# PIC32.net
KiCad netlist of a schematic drawn in EAGLE
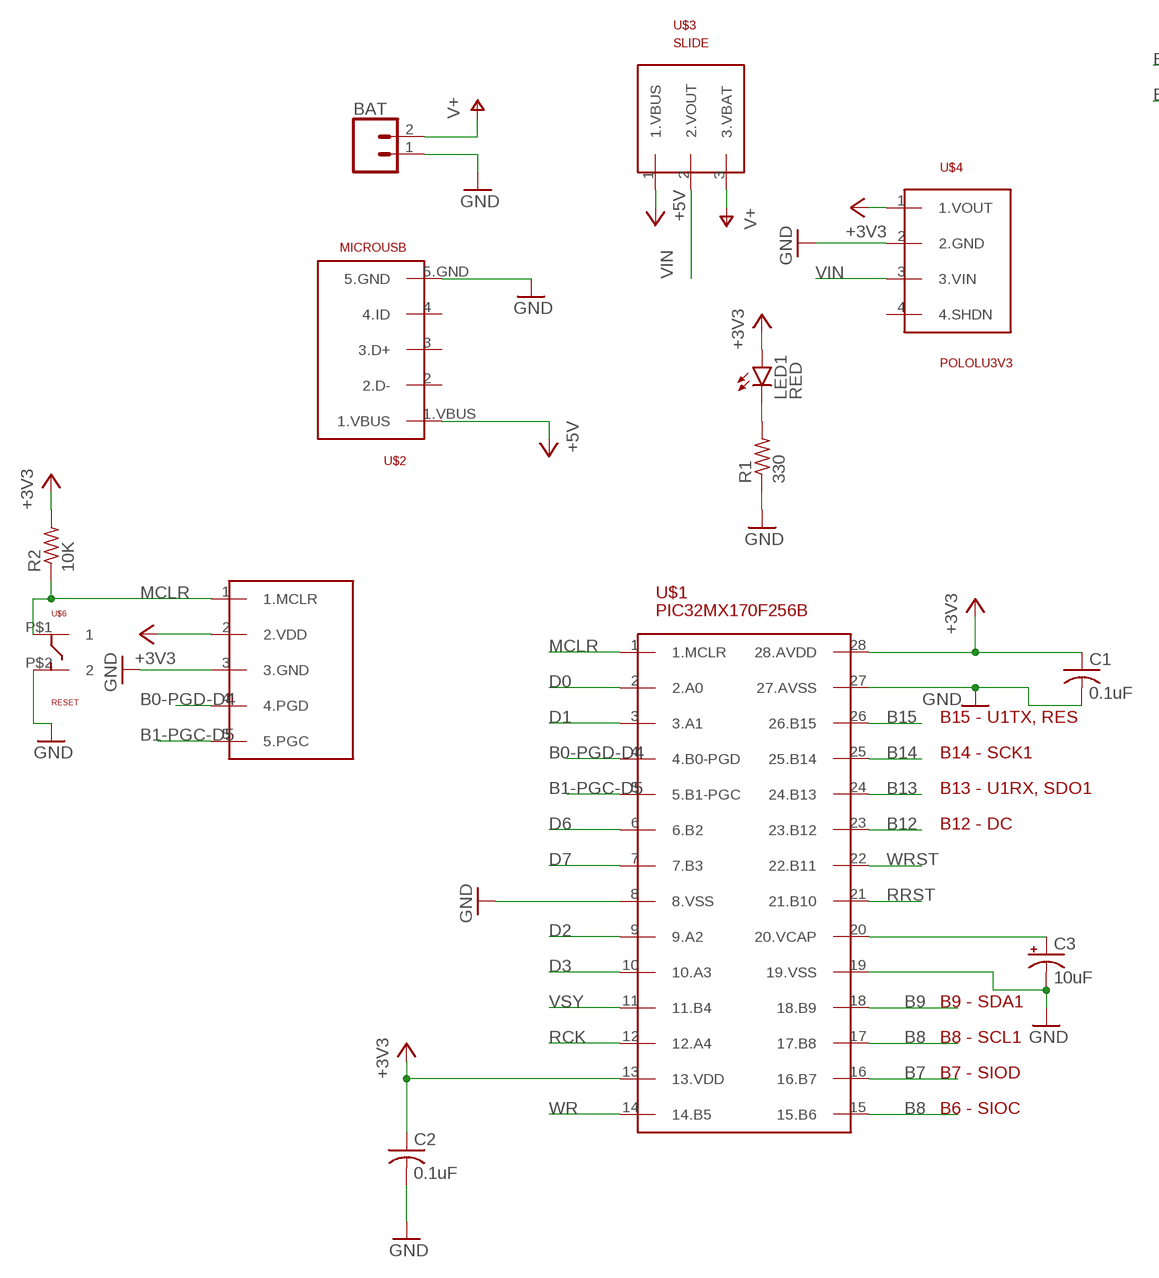
[diagram p0: schematic, sheet 1, part 1 of 2]
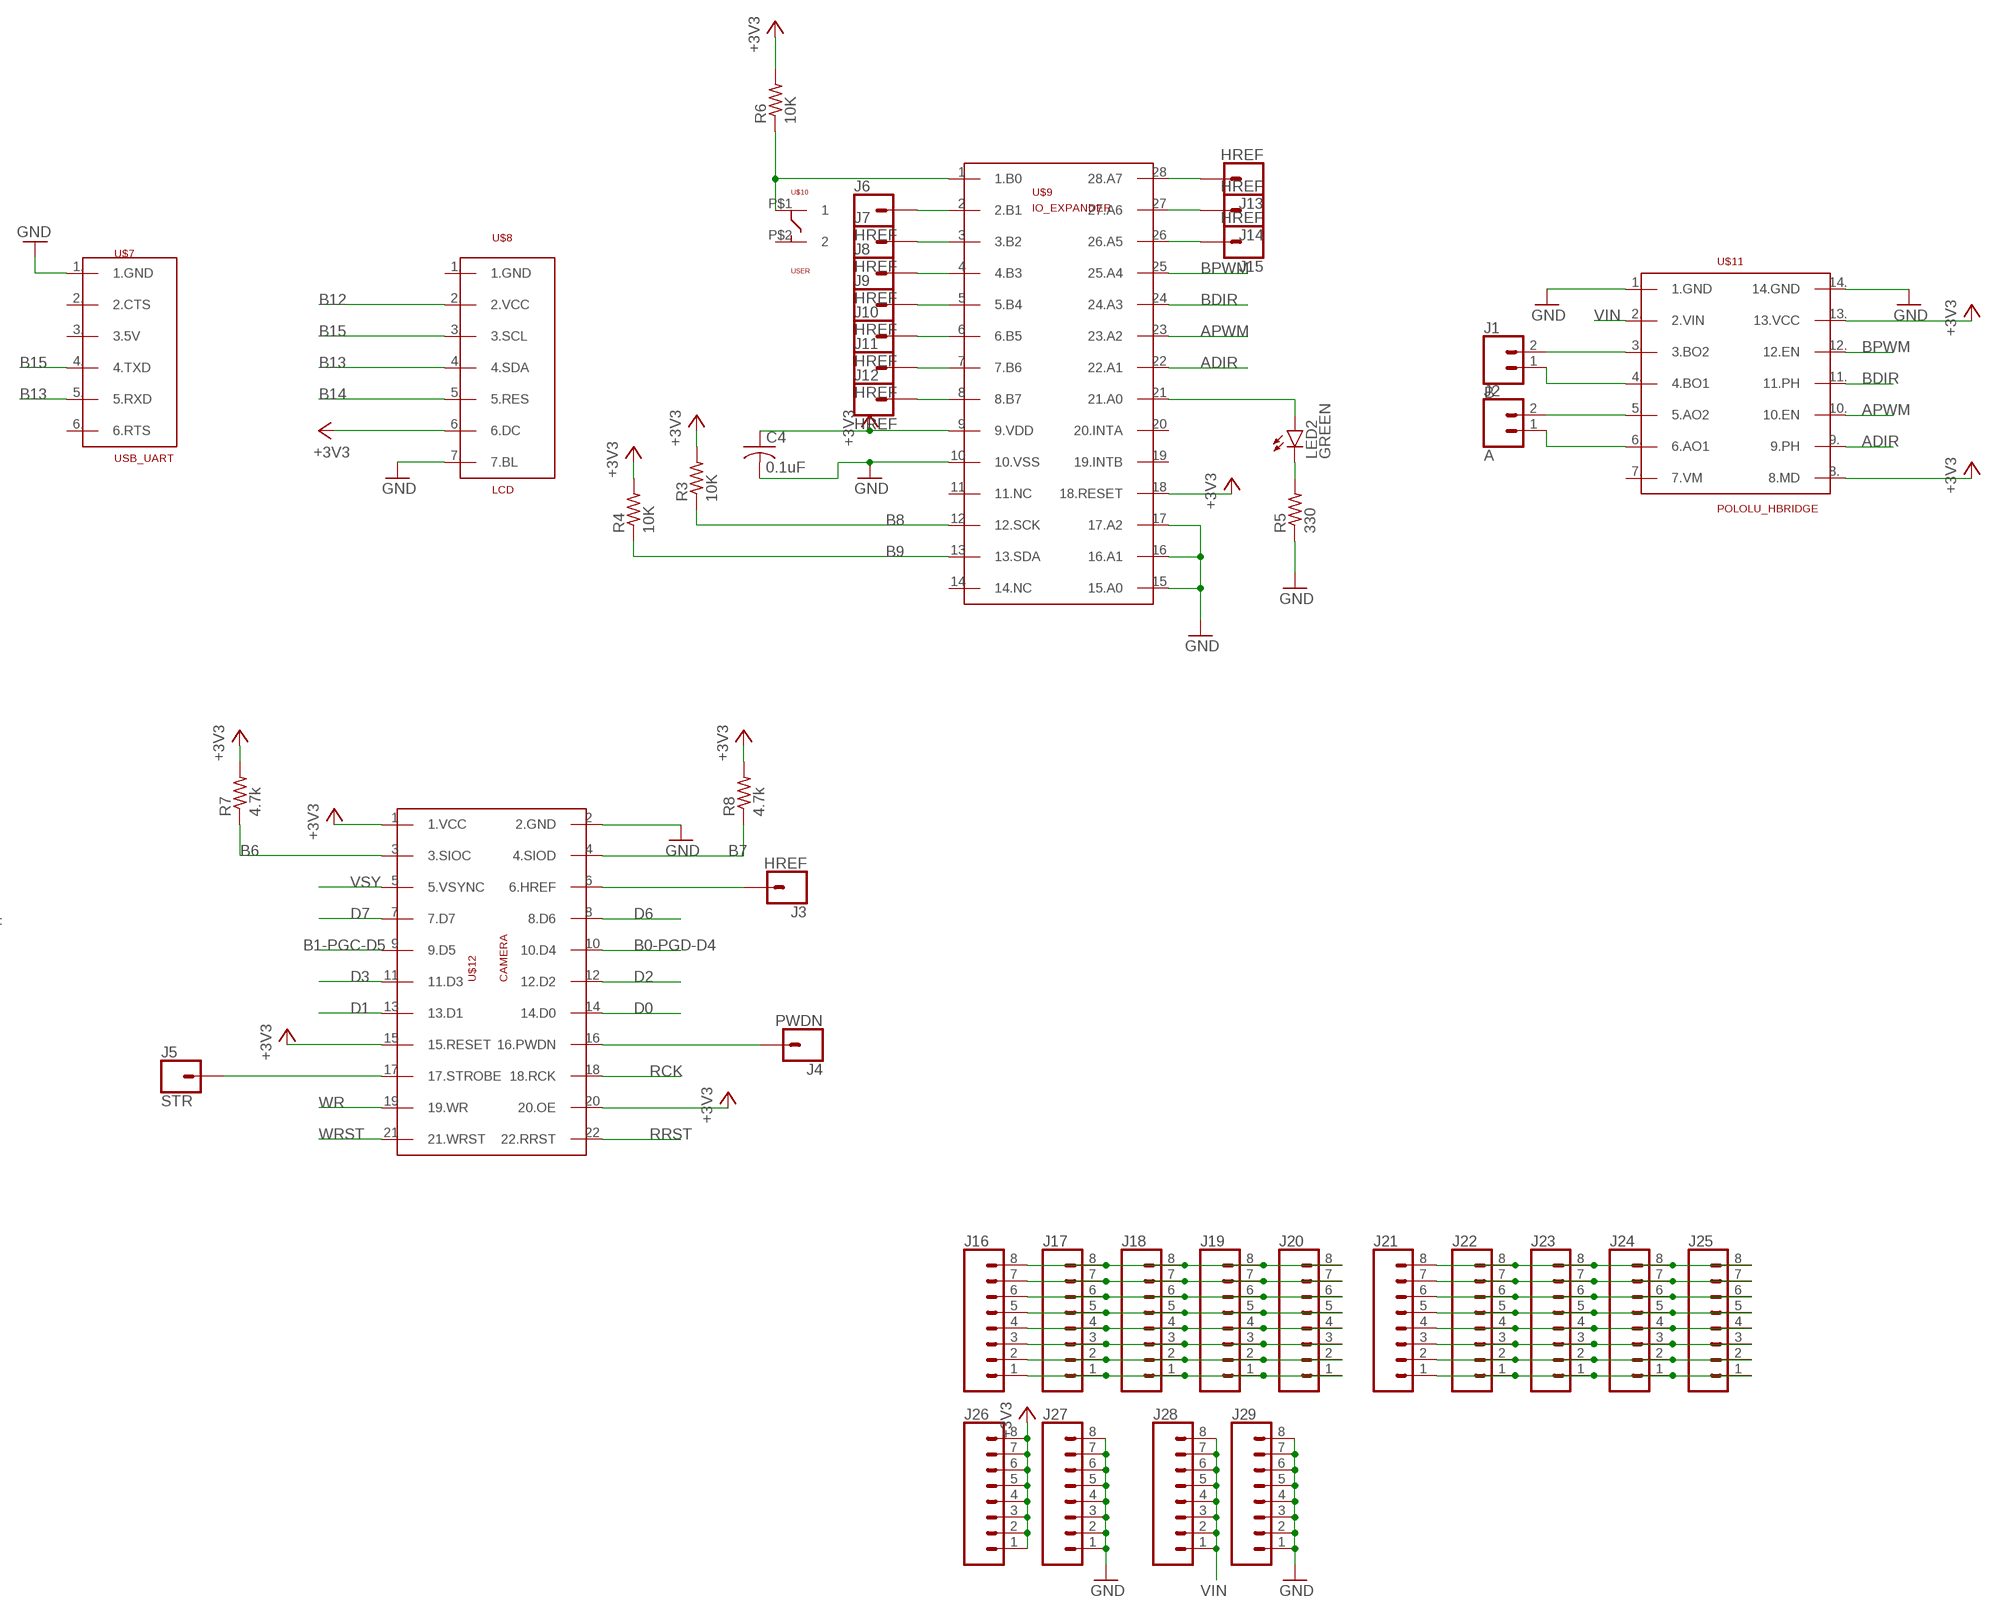
[diagram p1: schematic, sheet 1, part 2 of 2]

(export (version "E")
  (design (tool "Eeschema 10.0.6"))
  (components
    (comp (ref "BAT")
      (value "CONN_02")
      (footprint "eagle-import:1X02")
      (libsource (lib "eagle-import") (part "CONN_02"))
    )
    (comp (ref "C1")
      (value "0.1uF")
      (footprint "eagle-import:C025-025X050")
      (libsource (lib "eagle-import") (part "C-US025-025X050"))
    )
    (comp (ref "C2")
      (value "0.1uF")
      (footprint "eagle-import:C025-025X050")
      (libsource (lib "eagle-import") (part "C-US025-025X050"))
    )
    (comp (ref "C3")
      (value "10uF")
      (footprint "eagle-import:B45181B")
      (libsource (lib "eagle-import") (part "CPOL-USB45181B"))
    )
    (comp (ref "C4")
      (value "0.1uF")
      (footprint "eagle-import:C025-025X050")
      (libsource (lib "eagle-import") (part "C-US025-025X050"))
    )
    (comp (ref "J1")
      (value "B")
      (footprint "eagle-import:1X02")
      (libsource (lib "eagle-import") (part "CONN_02"))
    )
    (comp (ref "J2")
      (value "A")
      (footprint "eagle-import:1X02")
      (libsource (lib "eagle-import") (part "CONN_02"))
    )
    (comp (ref "J3")
      (value "HREF")
      (footprint "eagle-import:1X01")
      (libsource (lib "eagle-import") (part "CONN_01"))
    )
    (comp (ref "J4")
      (value "PWDN")
      (footprint "eagle-import:1X01")
      (libsource (lib "eagle-import") (part "CONN_01"))
    )
    (comp (ref "J5")
      (value "STR")
      (footprint "eagle-import:1X01")
      (libsource (lib "eagle-import") (part "CONN_01"))
    )
    (comp (ref "J6")
      (value "HREF")
      (footprint "eagle-import:1X01")
      (libsource (lib "eagle-import") (part "CONN_01"))
    )
    (comp (ref "J7")
      (value "HREF")
      (footprint "eagle-import:1X01")
      (libsource (lib "eagle-import") (part "CONN_01"))
    )
    (comp (ref "J8")
      (value "HREF")
      (footprint "eagle-import:1X01")
      (libsource (lib "eagle-import") (part "CONN_01"))
    )
    (comp (ref "J9")
      (value "HREF")
      (footprint "eagle-import:1X01")
      (libsource (lib "eagle-import") (part "CONN_01"))
    )
    (comp (ref "J10")
      (value "HREF")
      (footprint "eagle-import:1X01")
      (libsource (lib "eagle-import") (part "CONN_01"))
    )
    (comp (ref "J11")
      (value "HREF")
      (footprint "eagle-import:1X01")
      (libsource (lib "eagle-import") (part "CONN_01"))
    )
    (comp (ref "J12")
      (value "HREF")
      (footprint "eagle-import:1X01")
      (libsource (lib "eagle-import") (part "CONN_01"))
    )
    (comp (ref "J13")
      (value "HREF")
      (footprint "eagle-import:1X01")
      (libsource (lib "eagle-import") (part "CONN_01"))
    )
    (comp (ref "J14")
      (value "HREF")
      (footprint "eagle-import:1X01")
      (libsource (lib "eagle-import") (part "CONN_01"))
    )
    (comp (ref "J15")
      (value "HREF")
      (footprint "eagle-import:1X01")
      (libsource (lib "eagle-import") (part "CONN_01"))
    )
    (comp (ref "J16")
      (value "CONN_08\"")
      (footprint "eagle-import:1X08")
      (libsource (lib "eagle-import") (part "CONN_08{dblquote}"))
    )
    (comp (ref "J17")
      (value "CONN_08\"")
      (footprint "eagle-import:1X08")
      (libsource (lib "eagle-import") (part "CONN_08{dblquote}"))
    )
    (comp (ref "J18")
      (value "CONN_08\"")
      (footprint "eagle-import:1X08")
      (libsource (lib "eagle-import") (part "CONN_08{dblquote}"))
    )
    (comp (ref "J19")
      (value "CONN_08\"")
      (footprint "eagle-import:1X08")
      (libsource (lib "eagle-import") (part "CONN_08{dblquote}"))
    )
    (comp (ref "J20")
      (value "CONN_08\"")
      (footprint "eagle-import:1X08")
      (libsource (lib "eagle-import") (part "CONN_08{dblquote}"))
    )
    (comp (ref "J21")
      (value "CONN_08\"")
      (footprint "eagle-import:1X08")
      (libsource (lib "eagle-import") (part "CONN_08{dblquote}"))
    )
    (comp (ref "J22")
      (value "CONN_08\"")
      (footprint "eagle-import:1X08")
      (libsource (lib "eagle-import") (part "CONN_08{dblquote}"))
    )
    (comp (ref "J23")
      (value "CONN_08\"")
      (footprint "eagle-import:1X08")
      (libsource (lib "eagle-import") (part "CONN_08{dblquote}"))
    )
    (comp (ref "J24")
      (value "CONN_08\"")
      (footprint "eagle-import:1X08")
      (libsource (lib "eagle-import") (part "CONN_08{dblquote}"))
    )
    (comp (ref "J25")
      (value "CONN_08\"")
      (footprint "eagle-import:1X08")
      (libsource (lib "eagle-import") (part "CONN_08{dblquote}"))
    )
    (comp (ref "J26")
      (value "CONN_08\"")
      (footprint "eagle-import:1X08")
      (libsource (lib "eagle-import") (part "CONN_08{dblquote}"))
    )
    (comp (ref "J27")
      (value "CONN_08\"")
      (footprint "eagle-import:1X08")
      (libsource (lib "eagle-import") (part "CONN_08{dblquote}"))
    )
    (comp (ref "J28")
      (value "CONN_08\"")
      (footprint "eagle-import:1X08")
      (libsource (lib "eagle-import") (part "CONN_08{dblquote}"))
    )
    (comp (ref "J29")
      (value "CONN_08\"")
      (footprint "eagle-import:1X08")
      (libsource (lib "eagle-import") (part "CONN_08{dblquote}"))
    )
    (comp (ref "LED1")
      (value "RED")
      (footprint "eagle-import:LED3MM")
      (libsource (lib "eagle-import") (part "LED3MM"))
    )
    (comp (ref "LED2")
      (value "GREEN")
      (footprint "eagle-import:LED3MM")
      (libsource (lib "eagle-import") (part "LED3MM"))
    )
    (comp (ref "R1")
      (value "330")
      (footprint "eagle-import:0207_10")
      (libsource (lib "eagle-import") (part "R-US_0207/10"))
    )
    (comp (ref "R2")
      (value "10K")
      (footprint "eagle-import:0207_10")
      (libsource (lib "eagle-import") (part "R-US_0207/10"))
    )
    (comp (ref "R3")
      (value "10K")
      (footprint "eagle-import:0207_10")
      (libsource (lib "eagle-import") (part "R-US_0207/10"))
    )
    (comp (ref "R4")
      (value "10K")
      (footprint "eagle-import:0207_10")
      (libsource (lib "eagle-import") (part "R-US_0207/10"))
    )
    (comp (ref "R5")
      (value "330")
      (footprint "eagle-import:0207_10")
      (libsource (lib "eagle-import") (part "R-US_0207/10"))
    )
    (comp (ref "R6")
      (value "10K")
      (footprint "eagle-import:0207_10")
      (libsource (lib "eagle-import") (part "R-US_0207/10"))
    )
    (comp (ref "R7")
      (value "4.7k")
      (footprint "eagle-import:0207_10")
      (libsource (lib "eagle-import") (part "R-US_0207/10"))
    )
    (comp (ref "R8")
      (value "4.7k")
      (footprint "eagle-import:0207_10")
      (libsource (lib "eagle-import") (part "R-US_0207/10"))
    )
    (comp (ref "U$1")
      (value "PIC32MX170F256B")
      (footprint "eagle-import:DIL28-3")
      (libsource (lib "eagle-import") (part "PIC32MX170F256B"))
    )
    (comp (ref "U$2")
      (value "MICROUSB")
      (footprint "eagle-import:MICROUSB")
      (libsource (lib "eagle-import") (part "MICROUSB"))
    )
    (comp (ref "U$3")
      (value "SLIDE")
      (footprint "eagle-import:SLIDE")
      (libsource (lib "eagle-import") (part "SLIDE"))
    )
    (comp (ref "U$4")
      (value "POLOLU3V3")
      (footprint "eagle-import:POLOLU3V3")
      (libsource (lib "eagle-import") (part "POLOLU3V3"))
    )
    (comp (ref "U$5")
      (value "SNAP")
      (footprint "eagle-import:SNAP")
      (libsource (lib "eagle-import") (part "SNAP"))
    )
    (comp (ref "U$6")
      (value "RESET")
      (footprint "eagle-import:PUSH")
      (libsource (lib "eagle-import") (part "PUSH"))
    )
    (comp (ref "U$7")
      (value "USB_UART")
      (footprint "eagle-import:USB_UART")
      (libsource (lib "eagle-import") (part "USB_UART"))
    )
    (comp (ref "U$8")
      (value "LCD")
      (footprint "eagle-import:LCD")
      (libsource (lib "eagle-import") (part "LCD"))
    )
    (comp (ref "U$9")
      (value "IO_EXPANDER")
      (footprint "eagle-import:DIL28-3")
      (libsource (lib "eagle-import") (part "IO_EXPANDER"))
    )
    (comp (ref "U$10")
      (value "USER")
      (footprint "eagle-import:PUSH")
      (libsource (lib "eagle-import") (part "PUSH"))
    )
    (comp (ref "U$11")
      (value "POLOLU_HBRIDGE")
      (footprint "eagle-import:POLOLU_HBRIDGE")
      (libsource (lib "eagle-import") (part "POLOLU_HBRIDGE"))
    )
    (comp (ref "U$12")
      (value "CAMERA")
      (footprint "eagle-import:CAMERA")
      (libsource (lib "eagle-import") (part "CAMERA"))
    )
  )
  (nets
    (net (code "1") (name "+3V3") (class "Default")
      (node (ref "C1") (pin "1") (pinfunction "1_1") (pintype "passive"))
      (node (ref "C2") (pin "1") (pinfunction "1_1") (pintype "passive"))
      (node (ref "C4") (pin "1") (pinfunction "1_1") (pintype "passive"))
      (node (ref "J26") (pin "1") (pinfunction "1_1") (pintype "passive"))
      (node (ref "J26") (pin "2") (pinfunction "2_2") (pintype "passive"))
      (node (ref "J26") (pin "3") (pinfunction "3_3") (pintype "passive"))
      (node (ref "J26") (pin "4") (pinfunction "4_4") (pintype "passive"))
      (node (ref "J26") (pin "5") (pinfunction "5_5") (pintype "passive"))
      (node (ref "J26") (pin "6") (pinfunction "6_6") (pintype "passive"))
      (node (ref "J26") (pin "7") (pinfunction "7_7") (pintype "passive"))
      (node (ref "J26") (pin "8") (pinfunction "8_8") (pintype "passive"))
      (node (ref "LED1") (pin "A") (pinfunction "A_A") (pintype "passive"))
      (node (ref "R2") (pin "2") (pinfunction "2_2") (pintype "passive"))
      (node (ref "R3") (pin "2") (pinfunction "2_2") (pintype "passive"))
      (node (ref "R4") (pin "2") (pinfunction "2_2") (pintype "passive"))
      (node (ref "R6") (pin "2") (pinfunction "2_2") (pintype "passive"))
      (node (ref "R7") (pin "2") (pinfunction "2_2") (pintype "passive"))
      (node (ref "R8") (pin "2") (pinfunction "2_2") (pintype "passive"))
      (node (ref "U$1") (pin "13") (pinfunction "13.VDD_13") (pintype "bidirectional"))
      (node (ref "U$1") (pin "28") (pinfunction "28.AVDD_28") (pintype "bidirectional"))
      (node (ref "U$11") (pin "13.") (pinfunction "13.VCC_13.") (pintype "bidirectional"))
      (node (ref "U$11") (pin "8.") (pinfunction "8.MD_8.") (pintype "bidirectional"))
      (node (ref "U$12") (pin "1") (pinfunction "1.VCC_1") (pintype "bidirectional"))
      (node (ref "U$12") (pin "15") (pinfunction "15.RESET_15") (pintype "bidirectional"))
      (node (ref "U$12") (pin "20") (pinfunction "20.OE_20") (pintype "bidirectional"))
      (node (ref "U$4") (pin "1") (pinfunction "1.VOUT_1") (pintype "bidirectional"))
      (node (ref "U$5") (pin "2") (pinfunction "2.VDD_2") (pintype "bidirectional"))
      (node (ref "U$8") (pin "6.") (pinfunction "6.DC_6.") (pintype "bidirectional"))
      (node (ref "U$9") (pin "18") (pinfunction "18.RESET_18") (pintype "bidirectional"))
      (node (ref "U$9") (pin "9") (pinfunction "9.VDD_9") (pintype "bidirectional"))
    )
    (net (code "2") (name "+5V") (class "Default")
      (node (ref "U$2") (pin "1.VBUS") (pinfunction "1.VBUS_1.VBUS") (pintype "bidirectional"))
      (node (ref "U$3") (pin "1") (pinfunction "1.VBUS_1") (pintype "bidirectional"))
    )
    (net (code "3") (name "/ADIR") (class "Default")
      (node (ref "U$11") (pin "9.") (pinfunction "9.PH_9.") (pintype "bidirectional"))
      (node (ref "U$9") (pin "22") (pinfunction "22.A1_22") (pintype "bidirectional"))
    )
    (net (code "4") (name "/APWM") (class "Default")
      (node (ref "U$11") (pin "10.") (pinfunction "10.EN_10.") (pintype "bidirectional"))
      (node (ref "U$9") (pin "23") (pinfunction "23.A2_23") (pintype "bidirectional"))
    )
    (net (code "5") (name "/B0-PGD-D4") (class "Default")
      (node (ref "U$1") (pin "4") (pinfunction "4.B0-PGD_4") (pintype "bidirectional"))
      (node (ref "U$12") (pin "10") (pinfunction "10.D4_10") (pintype "bidirectional"))
      (node (ref "U$5") (pin "4") (pinfunction "4.PGD_4") (pintype "bidirectional"))
    )
    (net (code "6") (name "/B1-PGC-D5") (class "Default")
      (node (ref "U$1") (pin "5") (pinfunction "5.B1-PGC_5") (pintype "bidirectional"))
      (node (ref "U$12") (pin "9") (pinfunction "9.D5_9") (pintype "bidirectional"))
      (node (ref "U$5") (pin "5") (pinfunction "5.PGC_5") (pintype "bidirectional"))
    )
    (net (code "7") (name "/B6") (class "Default")
      (node (ref "R7") (pin "1") (pinfunction "1_1") (pintype "passive"))
      (node (ref "U$12") (pin "3") (pinfunction "3.SIOC_3") (pintype "bidirectional"))
    )
    (net (code "8") (name "/B7") (class "Default")
      (node (ref "R8") (pin "1") (pinfunction "1_1") (pintype "passive"))
      (node (ref "U$1") (pin "16") (pinfunction "16.B7_16") (pintype "bidirectional"))
      (node (ref "U$12") (pin "4") (pinfunction "4.SIOD_4") (pintype "bidirectional"))
    )
    (net (code "9") (name "/B8") (class "Default")
      (node (ref "R3") (pin "1") (pinfunction "1_1") (pintype "passive"))
      (node (ref "U$1") (pin "15") (pinfunction "15.B6_15") (pintype "bidirectional"))
      (node (ref "U$1") (pin "17") (pinfunction "17.B8_17") (pintype "bidirectional"))
      (node (ref "U$9") (pin "12") (pinfunction "12.SCK_12") (pintype "bidirectional"))
    )
    (net (code "10") (name "/B9") (class "Default")
      (node (ref "R4") (pin "1") (pinfunction "1_1") (pintype "passive"))
      (node (ref "U$1") (pin "18") (pinfunction "18.B9_18") (pintype "bidirectional"))
      (node (ref "U$9") (pin "13") (pinfunction "13.SDA_13") (pintype "bidirectional"))
    )
    (net (code "11") (name "/B12") (class "Default")
      (node (ref "U$1") (pin "23") (pinfunction "23.B12_23") (pintype "bidirectional"))
      (node (ref "U$8") (pin "2.") (pinfunction "2.VCC_2.") (pintype "bidirectional"))
    )
    (net (code "12") (name "/B13") (class "Default")
      (node (ref "U$1") (pin "24") (pinfunction "24.B13_24") (pintype "bidirectional"))
      (node (ref "U$7") (pin "5.") (pinfunction "5.RXD_5.") (pintype "bidirectional"))
      (node (ref "U$8") (pin "4.") (pinfunction "4.SDA_4.") (pintype "bidirectional"))
    )
    (net (code "13") (name "/B14") (class "Default")
      (node (ref "U$1") (pin "25") (pinfunction "25.B14_25") (pintype "bidirectional"))
      (node (ref "U$8") (pin "5.") (pinfunction "5.RES_5.") (pintype "bidirectional"))
    )
    (net (code "14") (name "/B15") (class "Default")
      (node (ref "U$1") (pin "26") (pinfunction "26.B15_26") (pintype "bidirectional"))
      (node (ref "U$7") (pin "4.") (pinfunction "4.TXD_4.") (pintype "bidirectional"))
      (node (ref "U$8") (pin "3.") (pinfunction "3.SCL_3.") (pintype "bidirectional"))
    )
    (net (code "15") (name "/BDIR") (class "Default")
      (node (ref "U$11") (pin "11.") (pinfunction "11.PH_11.") (pintype "bidirectional"))
      (node (ref "U$9") (pin "24") (pinfunction "24.A3_24") (pintype "bidirectional"))
    )
    (net (code "16") (name "/BPWM") (class "Default")
      (node (ref "U$11") (pin "12.") (pinfunction "12.EN_12.") (pintype "bidirectional"))
      (node (ref "U$9") (pin "25") (pinfunction "25.A4_25") (pintype "bidirectional"))
    )
    (net (code "17") (name "/D0") (class "Default")
      (node (ref "U$1") (pin "2") (pinfunction "2.A0_2") (pintype "bidirectional"))
      (node (ref "U$12") (pin "14") (pinfunction "14.D0_14") (pintype "bidirectional"))
    )
    (net (code "18") (name "/D1") (class "Default")
      (node (ref "U$1") (pin "3") (pinfunction "3.A1_3") (pintype "bidirectional"))
      (node (ref "U$12") (pin "13") (pinfunction "13.D1_13") (pintype "bidirectional"))
    )
    (net (code "19") (name "/D2") (class "Default")
      (node (ref "U$1") (pin "9") (pinfunction "9.A2_9") (pintype "bidirectional"))
      (node (ref "U$12") (pin "12") (pinfunction "12.D2_12") (pintype "bidirectional"))
    )
    (net (code "20") (name "/D3") (class "Default")
      (node (ref "U$1") (pin "10") (pinfunction "10.A3_10") (pintype "bidirectional"))
      (node (ref "U$12") (pin "11") (pinfunction "11.D3_11") (pintype "bidirectional"))
    )
    (net (code "21") (name "/D6") (class "Default")
      (node (ref "U$1") (pin "6") (pinfunction "6.B2_6") (pintype "bidirectional"))
      (node (ref "U$12") (pin "8") (pinfunction "8.D6_8") (pintype "bidirectional"))
    )
    (net (code "22") (name "/D7") (class "Default")
      (node (ref "U$1") (pin "7") (pinfunction "7.B3_7") (pintype "bidirectional"))
      (node (ref "U$12") (pin "7") (pinfunction "7.D7_7") (pintype "bidirectional"))
    )
    (net (code "23") (name "/MCLR") (class "Default")
      (node (ref "R2") (pin "1") (pinfunction "1_1") (pintype "passive"))
      (node (ref "U$1") (pin "1") (pinfunction "1.MCLR_1") (pintype "bidirectional"))
      (node (ref "U$5") (pin "1") (pinfunction "1.MCLR_1") (pintype "bidirectional"))
      (node (ref "U$6") (pin "P$1") (pinfunction "1_P$1") (pintype "bidirectional"))
    )
    (net (code "24") (name "/RCK") (class "Default")
      (node (ref "U$1") (pin "12") (pinfunction "12.A4_12") (pintype "bidirectional"))
      (node (ref "U$12") (pin "18") (pinfunction "18.RCK_18") (pintype "bidirectional"))
    )
    (net (code "25") (name "/RRST") (class "Default")
      (node (ref "U$1") (pin "21") (pinfunction "21.B10_21") (pintype "bidirectional"))
      (node (ref "U$12") (pin "22") (pinfunction "22.RRST_22") (pintype "bidirectional"))
    )
    (net (code "26") (name "/VIN") (class "Default")
      (node (ref "J28") (pin "1") (pinfunction "1_1") (pintype "passive"))
      (node (ref "J28") (pin "2") (pinfunction "2_2") (pintype "passive"))
      (node (ref "J28") (pin "3") (pinfunction "3_3") (pintype "passive"))
      (node (ref "J28") (pin "4") (pinfunction "4_4") (pintype "passive"))
      (node (ref "J28") (pin "5") (pinfunction "5_5") (pintype "passive"))
      (node (ref "J28") (pin "6") (pinfunction "6_6") (pintype "passive"))
      (node (ref "J28") (pin "7") (pinfunction "7_7") (pintype "passive"))
      (node (ref "J28") (pin "8") (pinfunction "8_8") (pintype "passive"))
      (node (ref "U$11") (pin "2.") (pinfunction "2.VIN_2.") (pintype "bidirectional"))
      (node (ref "U$3") (pin "2") (pinfunction "2.VOUT_2") (pintype "bidirectional"))
      (node (ref "U$4") (pin "3") (pinfunction "3.VIN_3") (pintype "bidirectional"))
    )
    (net (code "27") (name "/VSY") (class "Default")
      (node (ref "U$1") (pin "11") (pinfunction "11.B4_11") (pintype "bidirectional"))
      (node (ref "U$12") (pin "5") (pinfunction "5.VSYNC_5") (pintype "bidirectional"))
    )
    (net (code "28") (name "/WR") (class "Default")
      (node (ref "U$1") (pin "14") (pinfunction "14.B5_14") (pintype "bidirectional"))
      (node (ref "U$12") (pin "19") (pinfunction "19.WR_19") (pintype "bidirectional"))
    )
    (net (code "29") (name "/WRST") (class "Default")
      (node (ref "U$1") (pin "22") (pinfunction "22.B11_22") (pintype "bidirectional"))
      (node (ref "U$12") (pin "21") (pinfunction "21.WRST_21") (pintype "bidirectional"))
    )
    (net (code "30") (name "GND") (class "Default")
      (node (ref "BAT") (pin "1") (pinfunction "1_1") (pintype "passive"))
      (node (ref "C1") (pin "2") (pinfunction "2_2") (pintype "passive"))
      (node (ref "C2") (pin "2") (pinfunction "2_2") (pintype "passive"))
      (node (ref "C3") (pin "-") (pinfunction "-_-") (pintype "passive"))
      (node (ref "C4") (pin "2") (pinfunction "2_2") (pintype "passive"))
      (node (ref "J27") (pin "1") (pinfunction "1_1") (pintype "passive"))
      (node (ref "J27") (pin "2") (pinfunction "2_2") (pintype "passive"))
      (node (ref "J27") (pin "3") (pinfunction "3_3") (pintype "passive"))
      (node (ref "J27") (pin "4") (pinfunction "4_4") (pintype "passive"))
      (node (ref "J27") (pin "5") (pinfunction "5_5") (pintype "passive"))
      (node (ref "J27") (pin "6") (pinfunction "6_6") (pintype "passive"))
      (node (ref "J27") (pin "7") (pinfunction "7_7") (pintype "passive"))
      (node (ref "J27") (pin "8") (pinfunction "8_8") (pintype "passive"))
      (node (ref "J29") (pin "1") (pinfunction "1_1") (pintype "passive"))
      (node (ref "J29") (pin "2") (pinfunction "2_2") (pintype "passive"))
      (node (ref "J29") (pin "3") (pinfunction "3_3") (pintype "passive"))
      (node (ref "J29") (pin "4") (pinfunction "4_4") (pintype "passive"))
      (node (ref "J29") (pin "5") (pinfunction "5_5") (pintype "passive"))
      (node (ref "J29") (pin "6") (pinfunction "6_6") (pintype "passive"))
      (node (ref "J29") (pin "7") (pinfunction "7_7") (pintype "passive"))
      (node (ref "J29") (pin "8") (pinfunction "8_8") (pintype "passive"))
      (node (ref "R1") (pin "1") (pinfunction "1_1") (pintype "passive"))
      (node (ref "R5") (pin "1") (pinfunction "1_1") (pintype "passive"))
      (node (ref "U$1") (pin "19") (pinfunction "19.VSS_19") (pintype "bidirectional"))
      (node (ref "U$1") (pin "27") (pinfunction "27.AVSS_27") (pintype "bidirectional"))
      (node (ref "U$1") (pin "8") (pinfunction "8.VSS_8") (pintype "bidirectional"))
      (node (ref "U$11") (pin "1.") (pinfunction "1.GND_1.") (pintype "bidirectional"))
      (node (ref "U$11") (pin "14.") (pinfunction "14.GND_14.") (pintype "bidirectional"))
      (node (ref "U$12") (pin "2") (pinfunction "2.GND_2") (pintype "bidirectional"))
      (node (ref "U$2") (pin "5.GND") (pinfunction "5.GND_5.GND") (pintype "bidirectional"))
      (node (ref "U$4") (pin "2") (pinfunction "2.GND_2") (pintype "bidirectional"))
      (node (ref "U$5") (pin "3") (pinfunction "3.GND_3") (pintype "bidirectional"))
      (node (ref "U$6") (pin "P$2") (pinfunction "2_P$2") (pintype "bidirectional"))
      (node (ref "U$7") (pin "1.") (pinfunction "1.GND_1.") (pintype "bidirectional"))
      (node (ref "U$8") (pin "7.") (pinfunction "7.BL_7.") (pintype "bidirectional"))
      (node (ref "U$9") (pin "10") (pinfunction "10.VSS_10") (pintype "bidirectional"))
      (node (ref "U$9") (pin "15") (pinfunction "15.A0_15") (pintype "bidirectional"))
      (node (ref "U$9") (pin "16") (pinfunction "16.A1_16") (pintype "bidirectional"))
      (node (ref "U$9") (pin "17") (pinfunction "17.A2_17") (pintype "bidirectional"))
    )
    (net (code "31") (name "Net-(J16-Pad1)") (class "Default")
      (node (ref "J16") (pin "1") (pinfunction "1_1") (pintype "passive"))
      (node (ref "J17") (pin "1") (pinfunction "1_1") (pintype "passive"))
      (node (ref "J18") (pin "1") (pinfunction "1_1") (pintype "passive"))
      (node (ref "J19") (pin "1") (pinfunction "1_1") (pintype "passive"))
      (node (ref "J20") (pin "1") (pinfunction "1_1") (pintype "passive"))
    )
    (net (code "32") (name "Net-(J16-Pad2)") (class "Default")
      (node (ref "J16") (pin "2") (pinfunction "2_2") (pintype "passive"))
      (node (ref "J17") (pin "2") (pinfunction "2_2") (pintype "passive"))
      (node (ref "J18") (pin "2") (pinfunction "2_2") (pintype "passive"))
      (node (ref "J19") (pin "2") (pinfunction "2_2") (pintype "passive"))
      (node (ref "J20") (pin "2") (pinfunction "2_2") (pintype "passive"))
    )
    (net (code "33") (name "Net-(J16-Pad3)") (class "Default")
      (node (ref "J16") (pin "3") (pinfunction "3_3") (pintype "passive"))
      (node (ref "J17") (pin "3") (pinfunction "3_3") (pintype "passive"))
      (node (ref "J18") (pin "3") (pinfunction "3_3") (pintype "passive"))
      (node (ref "J19") (pin "3") (pinfunction "3_3") (pintype "passive"))
      (node (ref "J20") (pin "3") (pinfunction "3_3") (pintype "passive"))
    )
    (net (code "34") (name "Net-(J16-Pad4)") (class "Default")
      (node (ref "J16") (pin "4") (pinfunction "4_4") (pintype "passive"))
      (node (ref "J17") (pin "4") (pinfunction "4_4") (pintype "passive"))
      (node (ref "J18") (pin "4") (pinfunction "4_4") (pintype "passive"))
      (node (ref "J19") (pin "4") (pinfunction "4_4") (pintype "passive"))
      (node (ref "J20") (pin "4") (pinfunction "4_4") (pintype "passive"))
    )
    (net (code "35") (name "Net-(J16-Pad5)") (class "Default")
      (node (ref "J16") (pin "5") (pinfunction "5_5") (pintype "passive"))
      (node (ref "J17") (pin "5") (pinfunction "5_5") (pintype "passive"))
      (node (ref "J18") (pin "5") (pinfunction "5_5") (pintype "passive"))
      (node (ref "J19") (pin "5") (pinfunction "5_5") (pintype "passive"))
      (node (ref "J20") (pin "5") (pinfunction "5_5") (pintype "passive"))
    )
    (net (code "36") (name "Net-(J16-Pad6)") (class "Default")
      (node (ref "J16") (pin "6") (pinfunction "6_6") (pintype "passive"))
      (node (ref "J17") (pin "6") (pinfunction "6_6") (pintype "passive"))
      (node (ref "J18") (pin "6") (pinfunction "6_6") (pintype "passive"))
      (node (ref "J19") (pin "6") (pinfunction "6_6") (pintype "passive"))
      (node (ref "J20") (pin "6") (pinfunction "6_6") (pintype "passive"))
    )
    (net (code "37") (name "Net-(J16-Pad7)") (class "Default")
      (node (ref "J16") (pin "7") (pinfunction "7_7") (pintype "passive"))
      (node (ref "J17") (pin "7") (pinfunction "7_7") (pintype "passive"))
      (node (ref "J18") (pin "7") (pinfunction "7_7") (pintype "passive"))
      (node (ref "J19") (pin "7") (pinfunction "7_7") (pintype "passive"))
      (node (ref "J20") (pin "7") (pinfunction "7_7") (pintype "passive"))
    )
    (net (code "38") (name "Net-(J16-Pad8)") (class "Default")
      (node (ref "J16") (pin "8") (pinfunction "8_8") (pintype "passive"))
      (node (ref "J17") (pin "8") (pinfunction "8_8") (pintype "passive"))
      (node (ref "J18") (pin "8") (pinfunction "8_8") (pintype "passive"))
      (node (ref "J19") (pin "8") (pinfunction "8_8") (pintype "passive"))
      (node (ref "J20") (pin "8") (pinfunction "8_8") (pintype "passive"))
    )
    (net (code "39") (name "Net-(J21-Pad1)") (class "Default")
      (node (ref "J21") (pin "1") (pinfunction "1_1") (pintype "passive"))
      (node (ref "J22") (pin "1") (pinfunction "1_1") (pintype "passive"))
      (node (ref "J23") (pin "1") (pinfunction "1_1") (pintype "passive"))
      (node (ref "J24") (pin "1") (pinfunction "1_1") (pintype "passive"))
      (node (ref "J25") (pin "1") (pinfunction "1_1") (pintype "passive"))
    )
    (net (code "40") (name "Net-(J21-Pad2)") (class "Default")
      (node (ref "J21") (pin "2") (pinfunction "2_2") (pintype "passive"))
      (node (ref "J22") (pin "2") (pinfunction "2_2") (pintype "passive"))
      (node (ref "J23") (pin "2") (pinfunction "2_2") (pintype "passive"))
      (node (ref "J24") (pin "2") (pinfunction "2_2") (pintype "passive"))
      (node (ref "J25") (pin "2") (pinfunction "2_2") (pintype "passive"))
    )
    (net (code "41") (name "Net-(J21-Pad3)") (class "Default")
      (node (ref "J21") (pin "3") (pinfunction "3_3") (pintype "passive"))
      (node (ref "J22") (pin "3") (pinfunction "3_3") (pintype "passive"))
      (node (ref "J23") (pin "3") (pinfunction "3_3") (pintype "passive"))
      (node (ref "J24") (pin "3") (pinfunction "3_3") (pintype "passive"))
      (node (ref "J25") (pin "3") (pinfunction "3_3") (pintype "passive"))
    )
    (net (code "42") (name "Net-(J21-Pad4)") (class "Default")
      (node (ref "J21") (pin "4") (pinfunction "4_4") (pintype "passive"))
      (node (ref "J22") (pin "4") (pinfunction "4_4") (pintype "passive"))
      (node (ref "J23") (pin "4") (pinfunction "4_4") (pintype "passive"))
      (node (ref "J24") (pin "4") (pinfunction "4_4") (pintype "passive"))
      (node (ref "J25") (pin "4") (pinfunction "4_4") (pintype "passive"))
    )
    (net (code "43") (name "Net-(J21-Pad5)") (class "Default")
      (node (ref "J21") (pin "5") (pinfunction "5_5") (pintype "passive"))
      (node (ref "J22") (pin "5") (pinfunction "5_5") (pintype "passive"))
      (node (ref "J23") (pin "5") (pinfunction "5_5") (pintype "passive"))
      (node (ref "J24") (pin "5") (pinfunction "5_5") (pintype "passive"))
      (node (ref "J25") (pin "5") (pinfunction "5_5") (pintype "passive"))
    )
    (net (code "44") (name "Net-(J21-Pad6)") (class "Default")
      (node (ref "J21") (pin "6") (pinfunction "6_6") (pintype "passive"))
      (node (ref "J22") (pin "6") (pinfunction "6_6") (pintype "passive"))
      (node (ref "J23") (pin "6") (pinfunction "6_6") (pintype "passive"))
      (node (ref "J24") (pin "6") (pinfunction "6_6") (pintype "passive"))
      (node (ref "J25") (pin "6") (pinfunction "6_6") (pintype "passive"))
    )
    (net (code "45") (name "Net-(J21-Pad7)") (class "Default")
      (node (ref "J21") (pin "7") (pinfunction "7_7") (pintype "passive"))
      (node (ref "J22") (pin "7") (pinfunction "7_7") (pintype "passive"))
      (node (ref "J23") (pin "7") (pinfunction "7_7") (pintype "passive"))
      (node (ref "J24") (pin "7") (pinfunction "7_7") (pintype "passive"))
      (node (ref "J25") (pin "7") (pinfunction "7_7") (pintype "passive"))
    )
    (net (code "46") (name "Net-(J21-Pad8)") (class "Default")
      (node (ref "J21") (pin "8") (pinfunction "8_8") (pintype "passive"))
      (node (ref "J22") (pin "8") (pinfunction "8_8") (pintype "passive"))
      (node (ref "J23") (pin "8") (pinfunction "8_8") (pintype "passive"))
      (node (ref "J24") (pin "8") (pinfunction "8_8") (pintype "passive"))
      (node (ref "J25") (pin "8") (pinfunction "8_8") (pintype "passive"))
    )
    (net (code "47") (name "Net-(LED1-C)") (class "Default")
      (node (ref "LED1") (pin "K") (pinfunction "C_K") (pintype "passive"))
      (node (ref "R1") (pin "2") (pinfunction "2_2") (pintype "passive"))
    )
    (net (code "48") (name "Net-(LED2-C)") (class "Default")
      (node (ref "LED2") (pin "K") (pinfunction "C_K") (pintype "passive"))
      (node (ref "R5") (pin "2") (pinfunction "2_2") (pintype "passive"))
    )
    (net (code "49") (name "Net-(U$1-20.VCAP)") (class "Default")
      (node (ref "C3") (pin "+") (pinfunction "+_+") (pintype "passive"))
      (node (ref "U$1") (pin "20") (pinfunction "20.VCAP_20") (pintype "bidirectional"))
    )
    (net (code "50") (name "Net-(U$9-2.B1)") (class "Default")
      (node (ref "J6") (pin "1") (pinfunction "1_1") (pintype "passive"))
      (node (ref "U$9") (pin "2") (pinfunction "2.B1_2") (pintype "bidirectional"))
    )
    (net (code "51") (name "Net-(U$9-3.B2)") (class "Default")
      (node (ref "J7") (pin "1") (pinfunction "1_1") (pintype "passive"))
      (node (ref "U$9") (pin "3") (pinfunction "3.B2_3") (pintype "bidirectional"))
    )
    (net (code "52") (name "Net-(U$9-4.B3)") (class "Default")
      (node (ref "J8") (pin "1") (pinfunction "1_1") (pintype "passive"))
      (node (ref "U$9") (pin "4") (pinfunction "4.B3_4") (pintype "bidirectional"))
    )
    (net (code "53") (name "Net-(U$9-5.B4)") (class "Default")
      (node (ref "J9") (pin "1") (pinfunction "1_1") (pintype "passive"))
      (node (ref "U$9") (pin "5") (pinfunction "5.B4_5") (pintype "bidirectional"))
    )
    (net (code "54") (name "Net-(U$9-6.B5)") (class "Default")
      (node (ref "J10") (pin "1") (pinfunction "1_1") (pintype "passive"))
      (node (ref "U$9") (pin "6") (pinfunction "6.B5_6") (pintype "bidirectional"))
    )
    (net (code "55") (name "Net-(U$9-7.B6)") (class "Default")
      (node (ref "J11") (pin "1") (pinfunction "1_1") (pintype "passive"))
      (node (ref "U$9") (pin "7") (pinfunction "7.B6_7") (pintype "bidirectional"))
    )
    (net (code "56") (name "Net-(U$9-8.B7)") (class "Default")
      (node (ref "J12") (pin "1") (pinfunction "1_1") (pintype "passive"))
      (node (ref "U$9") (pin "8") (pinfunction "8.B7_8") (pintype "bidirectional"))
    )
    (net (code "57") (name "Net-(U$9-21.A0)") (class "Default")
      (node (ref "LED2") (pin "A") (pinfunction "A_A") (pintype "passive"))
      (node (ref "U$9") (pin "21") (pinfunction "21.A0_21") (pintype "bidirectional"))
    )
    (net (code "58") (name "Net-(U$9-26.A5)") (class "Default")
      (node (ref "J15") (pin "1") (pinfunction "1_1") (pintype "passive"))
      (node (ref "U$9") (pin "26") (pinfunction "26.A5_26") (pintype "bidirectional"))
    )
    (net (code "59") (name "Net-(U$9-27.A6)") (class "Default")
      (node (ref "J14") (pin "1") (pinfunction "1_1") (pintype "passive"))
      (node (ref "U$9") (pin "27") (pinfunction "27.A6_27") (pintype "bidirectional"))
    )
    (net (code "60") (name "Net-(U$9-28.A7)") (class "Default")
      (node (ref "J13") (pin "1") (pinfunction "1_1") (pintype "passive"))
      (node (ref "U$9") (pin "28") (pinfunction "28.A7_28") (pintype "bidirectional"))
    )
    (net (code "61") (name "Net-(U$10-1)") (class "Default")
      (node (ref "R6") (pin "1") (pinfunction "1_1") (pintype "passive"))
      (node (ref "U$10") (pin "P$1") (pinfunction "1_P$1") (pintype "bidirectional"))
      (node (ref "U$9") (pin "1") (pinfunction "1.B0_1") (pintype "bidirectional"))
    )
    (net (code "62") (name "Net-(U$11-3.BO2)") (class "Default")
      (node (ref "J1") (pin "2") (pinfunction "2_2") (pintype "passive"))
      (node (ref "U$11") (pin "3.") (pinfunction "3.BO2_3.") (pintype "bidirectional"))
    )
    (net (code "63") (name "Net-(U$11-4.BO1)") (class "Default")
      (node (ref "J1") (pin "1") (pinfunction "1_1") (pintype "passive"))
      (node (ref "U$11") (pin "4.") (pinfunction "4.BO1_4.") (pintype "bidirectional"))
    )
    (net (code "64") (name "Net-(U$11-5.AO2)") (class "Default")
      (node (ref "J2") (pin "2") (pinfunction "2_2") (pintype "passive"))
      (node (ref "U$11") (pin "5.") (pinfunction "5.AO2_5.") (pintype "bidirectional"))
    )
    (net (code "65") (name "Net-(U$11-6.AO1)") (class "Default")
      (node (ref "J2") (pin "1") (pinfunction "1_1") (pintype "passive"))
      (node (ref "U$11") (pin "6.") (pinfunction "6.AO1_6.") (pintype "bidirectional"))
    )
    (net (code "66") (name "Net-(U$12-6.HREF)") (class "Default")
      (node (ref "J3") (pin "1") (pinfunction "1_1") (pintype "passive"))
      (node (ref "U$12") (pin "6") (pinfunction "6.HREF_6") (pintype "bidirectional"))
    )
    (net (code "67") (name "Net-(U$12-16.PWDN)") (class "Default")
      (node (ref "J4") (pin "1") (pinfunction "1_1") (pintype "passive"))
      (node (ref "U$12") (pin "16") (pinfunction "16.PWDN_16") (pintype "bidirectional"))
    )
    (net (code "68") (name "Net-(U$12-17.STROBE)") (class "Default")
      (node (ref "J5") (pin "1") (pinfunction "1_1") (pintype "passive"))
      (node (ref "U$12") (pin "17") (pinfunction "17.STROBE_17") (pintype "bidirectional"))
    )
    (net (code "69") (name "V+") (class "Default")
      (node (ref "BAT") (pin "2") (pinfunction "2_2") (pintype "passive"))
      (node (ref "U$3") (pin "3") (pinfunction "3.VBAT_3") (pintype "bidirectional"))
    )
    (net (code "70") (name "unconnected-(U$2-2.D--Pad2)") (class "Default")
      (node (ref "U$2") (pin "2") (pinfunction "2.D-_2") (pintype "bidirectional"))
    )
    (net (code "71") (name "unconnected-(U$2-3.D+-Pad3)") (class "Default")
      (node (ref "U$2") (pin "3") (pinfunction "3.D+_3") (pintype "bidirectional"))
    )
    (net (code "72") (name "unconnected-(U$2-4.ID-Pad4)") (class "Default")
      (node (ref "U$2") (pin "4") (pinfunction "4.ID_4") (pintype "bidirectional"))
    )
    (net (code "73") (name "unconnected-(U$4-4.SHDN-Pad4)") (class "Default")
      (node (ref "U$4") (pin "4") (pinfunction "4.SHDN_4") (pintype "bidirectional"))
    )
    (net (code "74") (name "unconnected-(U$7-2.CTS-Pad2.)") (class "Default")
      (node (ref "U$7") (pin "2.") (pinfunction "2.CTS_2.") (pintype "bidirectional"))
    )
    (net (code "75") (name "unconnected-(U$7-3.5V-Pad3.)") (class "Default")
      (node (ref "U$7") (pin "3.") (pinfunction "3.5V_3.") (pintype "bidirectional"))
    )
    (net (code "76") (name "unconnected-(U$7-6.RTS-Pad6.)") (class "Default")
      (node (ref "U$7") (pin "6.") (pinfunction "6.RTS_6.") (pintype "bidirectional"))
    )
    (net (code "77") (name "unconnected-(U$8-1.GND-Pad1.)") (class "Default")
      (node (ref "U$8") (pin "1.") (pinfunction "1.GND_1.") (pintype "bidirectional"))
    )
    (net (code "78") (name "unconnected-(U$9-11.NC-Pad11)") (class "Default")
      (node (ref "U$9") (pin "11") (pinfunction "11.NC_11") (pintype "bidirectional"))
    )
    (net (code "79") (name "unconnected-(U$9-14.NC-Pad14)") (class "Default")
      (node (ref "U$9") (pin "14") (pinfunction "14.NC_14") (pintype "bidirectional"))
    )
    (net (code "80") (name "unconnected-(U$9-19.INTB-Pad19)") (class "Default")
      (node (ref "U$9") (pin "19") (pinfunction "19.INTB_19") (pintype "bidirectional"))
    )
    (net (code "81") (name "unconnected-(U$9-20.INTA-Pad20)") (class "Default")
      (node (ref "U$9") (pin "20") (pinfunction "20.INTA_20") (pintype "bidirectional"))
    )
    (net (code "82") (name "unconnected-(U$10-2-PadP$2)") (class "Default")
      (node (ref "U$10") (pin "P$2") (pinfunction "2_P$2") (pintype "bidirectional"))
    )
    (net (code "83") (name "unconnected-(U$11-7.VM-Pad7.)") (class "Default")
      (node (ref "U$11") (pin "7.") (pinfunction "7.VM_7.") (pintype "bidirectional"))
    )
  )
)
